# controller.net
KiCad netlist of a schematic drawn in EAGLE
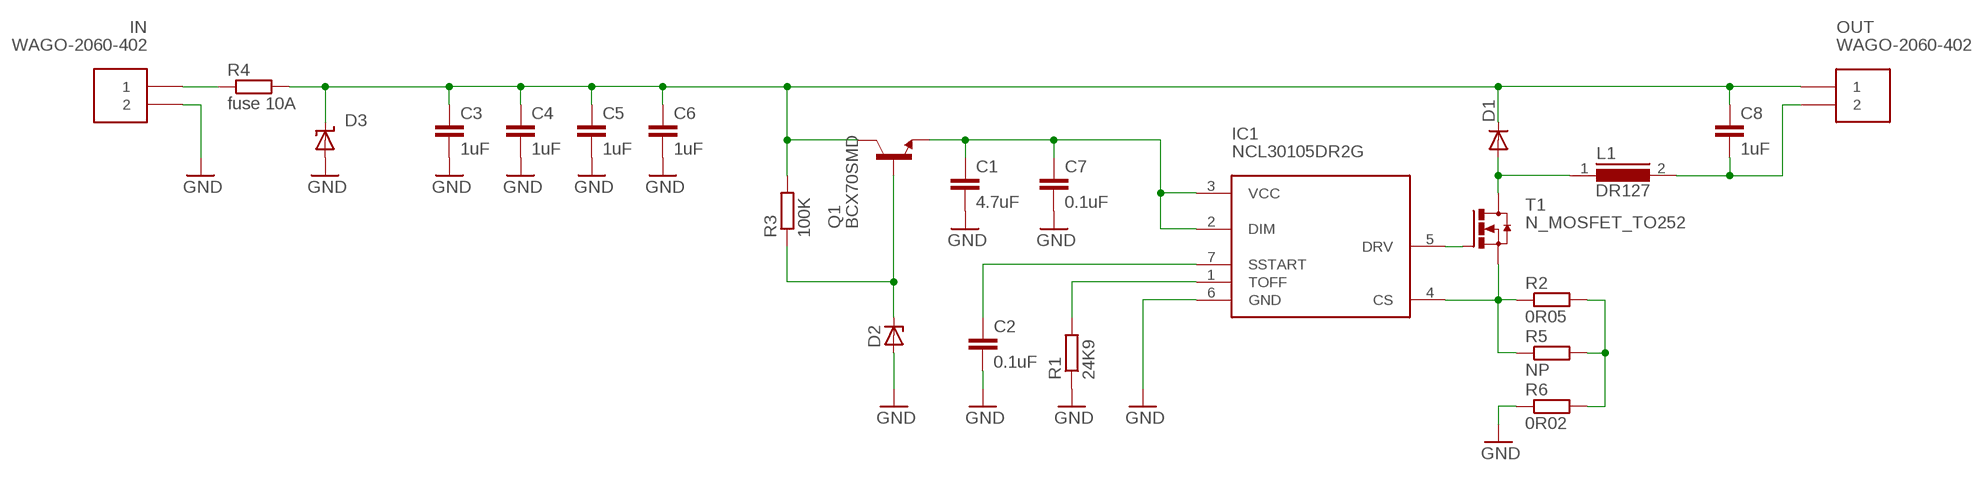
[diagram p0: schematic, sheet 1]

(export (version "E")
  (design (tool "Eeschema 10.0.6"))
  (components
    (comp (ref "C1")
      (value "4.7uF")
      (footprint "eagle-import:C0805")
      (libsource (lib "eagle-import") (part "C-EUC0805"))
    )
    (comp (ref "C2")
      (value "0.1uF")
      (footprint "eagle-import:C0603")
      (libsource (lib "eagle-import") (part "C-EUC0603"))
    )
    (comp (ref "C3")
      (value "1uF")
      (footprint "eagle-import:C1210")
      (libsource (lib "eagle-import") (part "C-EUC1210"))
    )
    (comp (ref "C4")
      (value "1uF")
      (footprint "eagle-import:C1210")
      (libsource (lib "eagle-import") (part "C-EUC1210"))
    )
    (comp (ref "C5")
      (value "1uF")
      (footprint "eagle-import:C1210")
      (libsource (lib "eagle-import") (part "C-EUC1210"))
    )
    (comp (ref "C6")
      (value "1uF")
      (footprint "eagle-import:C1210")
      (libsource (lib "eagle-import") (part "C-EUC1210"))
    )
    (comp (ref "C7")
      (value "0.1uF")
      (footprint "eagle-import:C0805")
      (libsource (lib "eagle-import") (part "C-EUC0805"))
    )
    (comp (ref "C8")
      (value "1uF")
      (footprint "eagle-import:C1210")
      (libsource (lib "eagle-import") (part "C-EUC1210"))
    )
    (comp (ref "D1")
      (value "DIODE-SMC")
      (footprint "eagle-import:SMC")
      (libsource (lib "eagle-import") (part "DIODE-SMC"))
    )
    (comp (ref "D2")
      (value "ZENER-DIODESOT23")
      (footprint "eagle-import:SOT23")
      (libsource (lib "eagle-import") (part "ZENER-DIODESOT23"))
    )
    (comp (ref "D3")
      (value "SUPPRESSOR-SMBJ")
      (footprint "eagle-import:SMBJ")
      (libsource (lib "eagle-import") (part "SUPPRESSOR-SMBJ"))
    )
    (comp (ref "IC1")
      (value "NCL30105DR2G")
      (footprint "eagle-import:SOIC8")
      (libsource (lib "eagle-import") (part "NCL30105DR2G"))
    )
    (comp (ref "IN")
      (value "WAGO-2060-402")
      (footprint "eagle-import:WAGO-2060-402")
      (libsource (lib "eagle-import") (part "WAGO-2060-402"))
    )
    (comp (ref "L1")
      (value "DR127")
      (footprint "eagle-import:DR127")
      (libsource (lib "eagle-import") (part "DR127"))
    )
    (comp (ref "OUT")
      (value "WAGO-2060-402")
      (footprint "eagle-import:WAGO-2060-402")
      (libsource (lib "eagle-import") (part "WAGO-2060-402"))
    )
    (comp (ref "Q1")
      (value "BCX70SMD")
      (footprint "eagle-import:SOT23")
      (libsource (lib "eagle-import") (part "BCX70SMD"))
    )
    (comp (ref "R1")
      (value "24K9")
      (footprint "eagle-import:R0603")
      (libsource (lib "eagle-import") (part "R-EU_R0603"))
    )
    (comp (ref "R2")
      (value "0R05")
      (footprint "eagle-import:R1210")
      (libsource (lib "eagle-import") (part "R-EU_R1210"))
    )
    (comp (ref "R3")
      (value "100K")
      (footprint "eagle-import:R1206")
      (libsource (lib "eagle-import") (part "R-EU_R1206"))
    )
    (comp (ref "R4")
      (value "fuse 10A")
      (footprint "eagle-import:R1206")
      (libsource (lib "eagle-import") (part "R-EU_R1206"))
    )
    (comp (ref "R5")
      (value "NP")
      (footprint "eagle-import:R1210")
      (libsource (lib "eagle-import") (part "R-EU_R1210"))
    )
    (comp (ref "R6")
      (value "0R02")
      (footprint "eagle-import:R1210")
      (libsource (lib "eagle-import") (part "R-EU_R1210"))
    )
    (comp (ref "T1")
      (value "N_MOSFET_TO252")
      (footprint "eagle-import:TO252")
      (libsource (lib "eagle-import") (part "N_MOSFET_TO252"))
    )
  )
  (nets
    (net (code "1") (name "GND") (class "Default")
      (node (ref "C1") (pin "2") (pinfunction "2_2") (pintype "passive"))
      (node (ref "C2") (pin "2") (pinfunction "2_2") (pintype "passive"))
      (node (ref "C3") (pin "2") (pinfunction "2_2") (pintype "passive"))
      (node (ref "C4") (pin "2") (pinfunction "2_2") (pintype "passive"))
      (node (ref "C5") (pin "2") (pinfunction "2_2") (pintype "passive"))
      (node (ref "C6") (pin "2") (pinfunction "2_2") (pintype "passive"))
      (node (ref "C7") (pin "2") (pinfunction "2_2") (pintype "passive"))
      (node (ref "D2") (pin "1") (pinfunction "A_1") (pintype "passive"))
      (node (ref "D3") (pin "A") (pinfunction "A_A") (pintype "passive"))
      (node (ref "IC1") (pin "6") (pinfunction "GND_6") (pintype "bidirectional"))
      (node (ref "IN") (pin "2_1") (pinfunction "2_2_1") (pintype "bidirectional"))
      (node (ref "IN") (pin "2_2") (pinfunction "2_2_2") (pintype "bidirectional"))
      (node (ref "R1") (pin "1") (pinfunction "1_1") (pintype "passive"))
      (node (ref "R6") (pin "1") (pinfunction "1_1") (pintype "passive"))
    )
    (net (code "2") (name "Net-(C8-Pad2)") (class "Default")
      (node (ref "C8") (pin "2") (pinfunction "2_2") (pintype "passive"))
      (node (ref "L1") (pin "2") (pinfunction "2_2") (pintype "passive"))
      (node (ref "OUT") (pin "2_1") (pinfunction "2_2_1") (pintype "bidirectional"))
      (node (ref "OUT") (pin "2_2") (pinfunction "2_2_2") (pintype "bidirectional"))
    )
    (net (code "3") (name "Net-(D2-C)") (class "Default")
      (node (ref "D2") (pin "3") (pinfunction "C_3") (pintype "passive"))
      (node (ref "Q1") (pin "1") (pinfunction "B_1") (pintype "passive"))
      (node (ref "R3") (pin "1") (pinfunction "1_1") (pintype "passive"))
    )
    (net (code "4") (name "Net-(IC1-CS)") (class "Default")
      (node (ref "IC1") (pin "4") (pinfunction "CS_4") (pintype "bidirectional"))
      (node (ref "R2") (pin "1") (pinfunction "1_1") (pintype "passive"))
      (node (ref "R5") (pin "1") (pinfunction "1_1") (pintype "passive"))
      (node (ref "T1") (pin "3") (pinfunction "S_3") (pintype "passive"))
    )
    (net (code "5") (name "Net-(IC1-DIM)") (class "Default")
      (node (ref "C1") (pin "1") (pinfunction "1_1") (pintype "passive"))
      (node (ref "C7") (pin "1") (pinfunction "1_1") (pintype "passive"))
      (node (ref "IC1") (pin "2") (pinfunction "DIM_2") (pintype "bidirectional"))
      (node (ref "IC1") (pin "3") (pinfunction "VCC_3") (pintype "bidirectional"))
      (node (ref "Q1") (pin "2") (pinfunction "E_2") (pintype "passive"))
    )
    (net (code "6") (name "Net-(IC1-DRV)") (class "Default")
      (node (ref "IC1") (pin "5") (pinfunction "DRV_5") (pintype "bidirectional"))
      (node (ref "T1") (pin "1") (pinfunction "G_1") (pintype "passive"))
    )
    (net (code "7") (name "Net-(IC1-SSTART)") (class "Default")
      (node (ref "C2") (pin "1") (pinfunction "1_1") (pintype "passive"))
      (node (ref "IC1") (pin "7") (pinfunction "SSTART_7") (pintype "bidirectional"))
    )
    (net (code "8") (name "Net-(IC1-TOFF)") (class "Default")
      (node (ref "IC1") (pin "1") (pinfunction "TOFF_1") (pintype "bidirectional"))
      (node (ref "R1") (pin "2") (pinfunction "2_2") (pintype "passive"))
    )
    (net (code "9") (name "Net-(IN-1-Pad1_1)") (class "Default")
      (node (ref "IN") (pin "1_1") (pinfunction "1_1_1") (pintype "bidirectional"))
      (node (ref "IN") (pin "1_2") (pinfunction "1_1_2") (pintype "bidirectional"))
      (node (ref "R4") (pin "1") (pinfunction "1_1") (pintype "passive"))
    )
    (net (code "10") (name "Net-(Q1-C)") (class "Default")
      (node (ref "C3") (pin "1") (pinfunction "1_1") (pintype "passive"))
      (node (ref "C4") (pin "1") (pinfunction "1_1") (pintype "passive"))
      (node (ref "C5") (pin "1") (pinfunction "1_1") (pintype "passive"))
      (node (ref "C6") (pin "1") (pinfunction "1_1") (pintype "passive"))
      (node (ref "C8") (pin "1") (pinfunction "1_1") (pintype "passive"))
      (node (ref "D1") (pin "C") (pinfunction "C_C") (pintype "passive"))
      (node (ref "D3") (pin "C") (pinfunction "C_C") (pintype "passive"))
      (node (ref "OUT") (pin "1_1") (pinfunction "1_1_1") (pintype "bidirectional"))
      (node (ref "OUT") (pin "1_2") (pinfunction "1_1_2") (pintype "bidirectional"))
      (node (ref "Q1") (pin "3") (pinfunction "C_3") (pintype "passive"))
      (node (ref "R3") (pin "2") (pinfunction "2_2") (pintype "passive"))
      (node (ref "R4") (pin "2") (pinfunction "2_2") (pintype "passive"))
    )
    (net (code "11") (name "Net-(R2-Pad2)") (class "Default")
      (node (ref "R2") (pin "2") (pinfunction "2_2") (pintype "passive"))
      (node (ref "R5") (pin "2") (pinfunction "2_2") (pintype "passive"))
      (node (ref "R6") (pin "2") (pinfunction "2_2") (pintype "passive"))
    )
    (net (code "12") (name "Net-(T1-D)") (class "Default")
      (node (ref "D1") (pin "A") (pinfunction "A_A") (pintype "passive"))
      (node (ref "L1") (pin "1") (pinfunction "1_1") (pintype "passive"))
      (node (ref "T1") (pin "4") (pinfunction "D_4") (pintype "passive"))
    )
  )
)
